# Input.net
KiCad netlist of a schematic drawn in Altium Designer
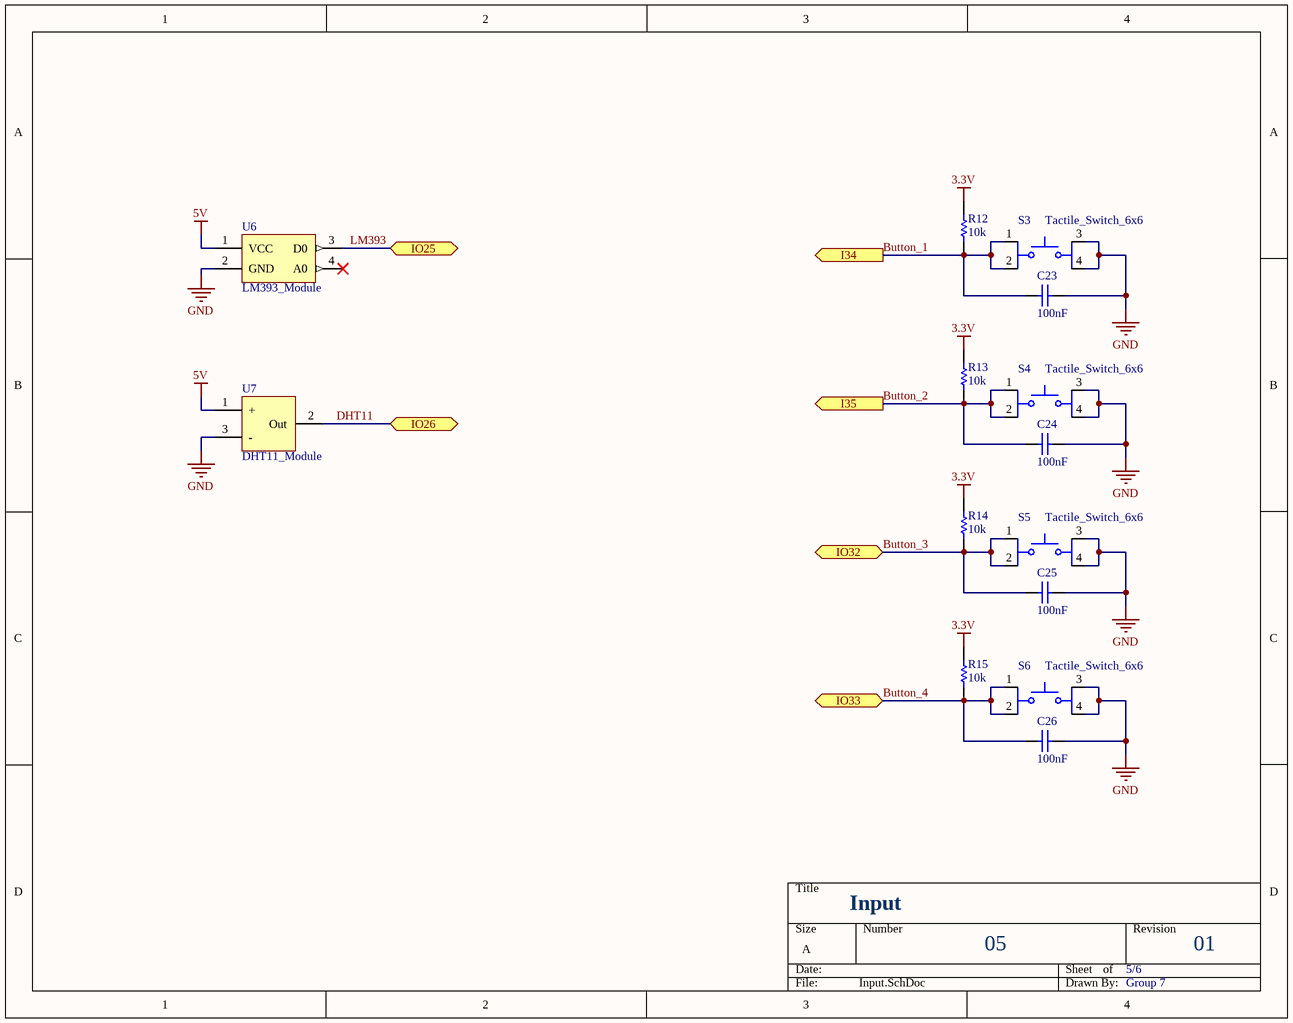
[diagram p0:  Input.SchDoc]

(export (version "E")
  (design (tool "Eeschema 10.0.6"))
  (components
    (comp (ref "C23")
      (value "100nF")
      (footprint "CAP_0603")
      (description "CAP, size 0603, 100nF")
      (libsource (lib "SMIOT_Lib_Schematic") (part "01060310410"))
    )
    (comp (ref "C24")
      (value "100nF")
      (footprint "CAP_0603")
      (description "CAP, size 0603, 100nF")
      (libsource (lib "SMIOT_Lib_Schematic") (part "01060310410"))
    )
    (comp (ref "C25")
      (value "100nF")
      (footprint "CAP_0603")
      (description "CAP, size 0603, 100nF")
      (libsource (lib "SMIOT_Lib_Schematic") (part "01060310410"))
    )
    (comp (ref "C26")
      (value "100nF")
      (footprint "CAP_0603")
      (description "CAP, size 0603, 100nF")
      (libsource (lib "SMIOT_Lib_Schematic") (part "01060310410"))
    )
    (comp (ref "R12")
      (value "10k")
      (footprint "resistor_0603")
      (description "RES, 10k Ohm, size 0603, 1%")
      (libsource (lib "SMIOT_Lib_Schematic") (part "0006031031"))
    )
    (comp (ref "R13")
      (value "10k")
      (footprint "resistor_0603")
      (description "RES, 10k Ohm, size 0603, 1%")
      (libsource (lib "SMIOT_Lib_Schematic") (part "0006031031"))
    )
    (comp (ref "R14")
      (value "10k")
      (footprint "resistor_0603")
      (description "RES, 10k Ohm, size 0603, 1%")
      (libsource (lib "SMIOT_Lib_Schematic") (part "0006031031"))
    )
    (comp (ref "R15")
      (value "10k")
      (footprint "resistor_0603")
      (description "RES, 10k Ohm, size 0603, 1%")
      (libsource (lib "SMIOT_Lib_Schematic") (part "0006031031"))
    )
    (comp (ref "S3")
      (value "Tactile_Switch_6x6")
      (footprint "Tactile_Switch_6x6")
      (description "Tactile Switch, 6x6mm")
      (libsource (lib "SMIOT_Lib_Schematic") (part "Tactile_Switch_6x6"))
    )
    (comp (ref "S4")
      (value "Tactile_Switch_6x6")
      (footprint "Tactile_Switch_6x6")
      (description "Tactile Switch, 6x6mm")
      (libsource (lib "SMIOT_Lib_Schematic") (part "Tactile_Switch_6x6"))
    )
    (comp (ref "S5")
      (value "Tactile_Switch_6x6")
      (footprint "Tactile_Switch_6x6")
      (description "Tactile Switch, 6x6mm")
      (libsource (lib "SMIOT_Lib_Schematic") (part "Tactile_Switch_6x6"))
    )
    (comp (ref "S6")
      (value "Tactile_Switch_6x6")
      (footprint "Tactile_Switch_6x6")
      (description "Tactile Switch, 6x6mm")
      (libsource (lib "SMIOT_Lib_Schematic") (part "Tactile_Switch_6x6"))
    )
    (comp (ref "U6")
      (value "LM393_Module")
      (footprint "Flame Sensor")
      (description "Flame Sensor, 3.3V-5V, infrared, ouput: analog/digital.")
      (libsource (lib "SMIOT_Lib_Schematic") (part "LM393_Module"))
    )
    (comp (ref "U7")
      (value "DHT11_Module")
      (footprint "DHT11_Module")
      (description "Temperature & Humidity Sensor, 3.3V-5V, 5mA")
      (libsource (lib "SMIOT_Lib_Schematic") (part "DHT11_Module"))
    )
  )
  (nets
    (net (code "1") (name "/Button_1") (class "Default")
      (node (ref "C23") (pin "1") (pinfunction "1_1") (pintype "passive"))
      (node (ref "R12") (pin "2") (pinfunction "2_2") (pintype "passive"))
      (node (ref "S3") (pin "1") (pinfunction "1_1") (pintype "passive"))
      (node (ref "S3") (pin "2") (pinfunction "2_2") (pintype "passive"))
    )
    (net (code "2") (name "/Button_2") (class "Default")
      (node (ref "C24") (pin "1") (pinfunction "1_1") (pintype "passive"))
      (node (ref "R13") (pin "2") (pinfunction "2_2") (pintype "passive"))
      (node (ref "S4") (pin "1") (pinfunction "1_1") (pintype "passive"))
      (node (ref "S4") (pin "2") (pinfunction "2_2") (pintype "passive"))
    )
    (net (code "3") (name "/Button_3") (class "Default")
      (node (ref "C25") (pin "1") (pinfunction "1_1") (pintype "passive"))
      (node (ref "R14") (pin "2") (pinfunction "2_2") (pintype "passive"))
      (node (ref "S5") (pin "1") (pinfunction "1_1") (pintype "passive"))
      (node (ref "S5") (pin "2") (pinfunction "2_2") (pintype "passive"))
    )
    (net (code "4") (name "/Button_4") (class "Default")
      (node (ref "C26") (pin "1") (pinfunction "1_1") (pintype "passive"))
      (node (ref "R15") (pin "2") (pinfunction "2_2") (pintype "passive"))
      (node (ref "S6") (pin "1") (pinfunction "1_1") (pintype "passive"))
      (node (ref "S6") (pin "2") (pinfunction "2_2") (pintype "passive"))
    )
    (net (code "5") (name "/DHT11") (class "Default")
      (node (ref "U7") (pin "2") (pinfunction "Out_2") (pintype "passive"))
    )
    (net (code "6") (name "/LM393") (class "Default")
      (node (ref "U6") (pin "3") (pinfunction "D0_3") (pintype "output"))
    )
    (net (code "7") (name "3.3V") (class "Default")
      (node (ref "R12") (pin "1") (pinfunction "1_1") (pintype "passive"))
      (node (ref "R13") (pin "1") (pinfunction "1_1") (pintype "passive"))
      (node (ref "R14") (pin "1") (pinfunction "1_1") (pintype "passive"))
      (node (ref "R15") (pin "1") (pinfunction "1_1") (pintype "passive"))
    )
    (net (code "8") (name "5V") (class "Default")
      (node (ref "U6") (pin "1") (pinfunction "VCC_1") (pintype "power_in"))
      (node (ref "U7") (pin "1") (pinfunction "+_1") (pintype "passive"))
    )
    (net (code "9") (name "GND") (class "Default")
      (node (ref "C23") (pin "2") (pinfunction "2_2") (pintype "passive"))
      (node (ref "C24") (pin "2") (pinfunction "2_2") (pintype "passive"))
      (node (ref "C25") (pin "2") (pinfunction "2_2") (pintype "passive"))
      (node (ref "C26") (pin "2") (pinfunction "2_2") (pintype "passive"))
      (node (ref "S3") (pin "3") (pinfunction "3_3") (pintype "passive"))
      (node (ref "S3") (pin "4") (pinfunction "4_4") (pintype "passive"))
      (node (ref "S4") (pin "3") (pinfunction "3_3") (pintype "passive"))
      (node (ref "S4") (pin "4") (pinfunction "4_4") (pintype "passive"))
      (node (ref "S5") (pin "3") (pinfunction "3_3") (pintype "passive"))
      (node (ref "S5") (pin "4") (pinfunction "4_4") (pintype "passive"))
      (node (ref "S6") (pin "3") (pinfunction "3_3") (pintype "passive"))
      (node (ref "S6") (pin "4") (pinfunction "4_4") (pintype "passive"))
      (node (ref "U6") (pin "2") (pinfunction "GND_2") (pintype "power_in"))
      (node (ref "U7") (pin "3") (pinfunction "-_3") (pintype "power_in"))
    )
    (net (code "10") (name "unconnected-(U6-A0-Pad4)") (class "Default")
      (node (ref "U6") (pin "4") (pinfunction "A0_4") (pintype "output+no_connect"))
    )
  )
)
